# Main_PLL.net
KiCad netlist of a schematic drawn in Altium Designer
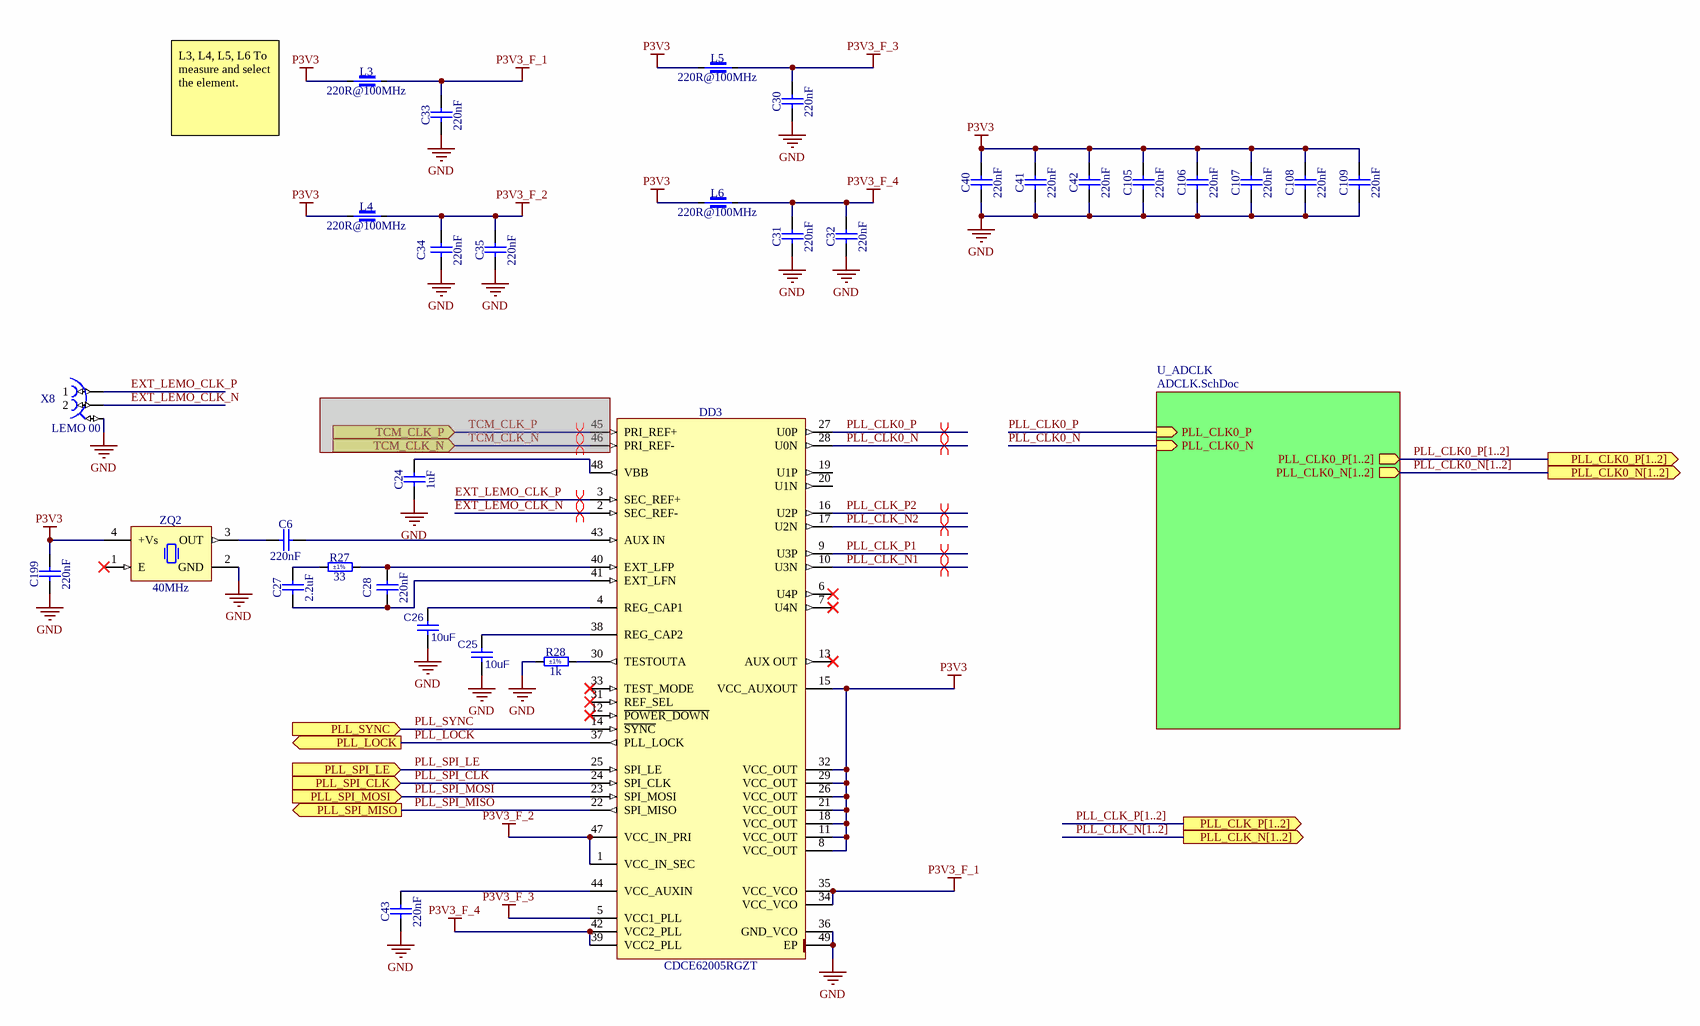
[diagram p0: Main_PLL.SchDoc]

(export (version "E")
  (design (tool "Eeschema 10.0.6"))
  (components
    (comp (ref "C6")
      (value "220nF")
      (footprint "CAPC1005X55N")
      (description "Non-polarised capacitor")
      (fields
        (field (name "PART NUMBER") "CC0402_220NF_16V_10%_X7R")
        (field (name "VOLTAGE") "16V")
        (field (name "AUTHOR") "CERN DEM JLC")
      )
      (libsource (lib "Capacitors") (part "Capacitor - non polarized"))
    )
    (comp (ref "C24")
      (value "1uF")
      (footprint "CAPC2012X140N")
      (description "Non-polarised capacitor")
      (fields
        (field (name "PART NUMBER") "CC0805_1UF_25V_10%_X7R")
        (field (name "VOLTAGE") "25V")
        (field (name "AUTHOR") "CERN DEM JLC")
      )
      (libsource (lib "Capacitors") (part "Capacitor - non polarized"))
    )
    (comp (ref "C25")
      (value "10uF")
      (footprint "CAPC1005X70N")
      (description "Non-polarised capacitor")
      (fields
        (field (name "PART NUMBER") "CC0402_10UF_6.3V_20%_X5R")
        (field (name "VOLTAGE") "6.3V")
        (field (name "AUTHOR") "CERN DEM JLC")
      )
      (libsource (lib "Capacitors") (part "Capacitor - non polarized"))
    )
    (comp (ref "C26")
      (value "10uF")
      (footprint "CAPC1005X70N")
      (description "Non-polarised capacitor")
      (fields
        (field (name "PART NUMBER") "CC0402_10UF_6.3V_20%_X5R")
        (field (name "VOLTAGE") "6.3V")
        (field (name "AUTHOR") "CERN DEM JLC")
      )
      (libsource (lib "Capacitors") (part "Capacitor - non polarized"))
    )
    (comp (ref "C27")
      (value "2.2uF")
      (footprint "CAPC2012X140N")
      (description "Non-polarised capacitor")
      (fields
        (field (name "PART NUMBER") "CC0805_2.2UF_50V_10%_X7R")
        (field (name "VOLTAGE") "50V")
        (field (name "AUTHOR") "CERN DEM JLC")
      )
      (libsource (lib "Capacitors") (part "Capacitor - non polarized"))
    )
    (comp (ref "C28")
      (value "220nF")
      (footprint "CAPC2012X135N")
      (description "Non-polarised capacitor")
      (fields
        (field (name "PART NUMBER") "CC0805_220NF_50V_10%_X7R")
        (field (name "VOLTAGE") "50V")
        (field (name "AUTHOR") "CERN DEM JLC")
      )
      (libsource (lib "Capacitors") (part "Capacitor - non polarized"))
    )
    (comp (ref "C30")
      (value "220nF")
      (footprint "CAPC2012X135N")
      (description "Non-polarised capacitor")
      (fields
        (field (name "PART NUMBER") "CC0805_220NF_50V_10%_X7R")
        (field (name "VOLTAGE") "50V")
        (field (name "AUTHOR") "CERN DEM JLC")
      )
      (libsource (lib "Capacitors") (part "Capacitor - non polarized"))
    )
    (comp (ref "C31")
      (value "220nF")
      (footprint "CAPC2012X135N")
      (description "Non-polarised capacitor")
      (fields
        (field (name "PART NUMBER") "CC0805_220NF_50V_10%_X7R")
        (field (name "VOLTAGE") "50V")
        (field (name "AUTHOR") "CERN DEM JLC")
      )
      (libsource (lib "Capacitors") (part "Capacitor - non polarized"))
    )
    (comp (ref "C32")
      (value "220nF")
      (footprint "CAPC2012X135N")
      (description "Non-polarised capacitor")
      (fields
        (field (name "PART NUMBER") "CC0805_220NF_50V_10%_X7R")
        (field (name "VOLTAGE") "50V")
        (field (name "AUTHOR") "CERN DEM JLC")
      )
      (libsource (lib "Capacitors") (part "Capacitor - non polarized"))
    )
    (comp (ref "C33")
      (value "220nF")
      (footprint "CAPC2012X135N")
      (description "Non-polarised capacitor")
      (fields
        (field (name "PART NUMBER") "CC0805_220NF_50V_10%_X7R")
        (field (name "VOLTAGE") "50V")
        (field (name "AUTHOR") "CERN DEM JLC")
      )
      (libsource (lib "Capacitors") (part "Capacitor - non polarized"))
    )
    (comp (ref "C34")
      (value "220nF")
      (footprint "CAPC2012X135N")
      (description "Non-polarised capacitor")
      (fields
        (field (name "PART NUMBER") "CC0805_220NF_50V_10%_X7R")
        (field (name "VOLTAGE") "50V")
        (field (name "AUTHOR") "CERN DEM JLC")
      )
      (libsource (lib "Capacitors") (part "Capacitor - non polarized"))
    )
    (comp (ref "C35")
      (value "220nF")
      (footprint "CAPC2012X135N")
      (description "Non-polarised capacitor")
      (fields
        (field (name "PART NUMBER") "CC0805_220NF_50V_10%_X7R")
        (field (name "VOLTAGE") "50V")
        (field (name "AUTHOR") "CERN DEM JLC")
      )
      (libsource (lib "Capacitors") (part "Capacitor - non polarized"))
    )
    (comp (ref "C40")
      (value "220nF")
      (footprint "CAPC1005X55N")
      (description "Non-polarised capacitor")
      (fields
        (field (name "PART NUMBER") "CC0402_220NF_16V_10%_X7R")
        (field (name "VOLTAGE") "16V")
        (field (name "AUTHOR") "CERN DEM JLC")
      )
      (libsource (lib "Capacitors") (part "Capacitor - non polarized"))
    )
    (comp (ref "C41")
      (value "220nF")
      (footprint "CAPC1005X55N")
      (description "Non-polarised capacitor")
      (fields
        (field (name "PART NUMBER") "CC0402_220NF_16V_10%_X7R")
        (field (name "VOLTAGE") "16V")
        (field (name "AUTHOR") "CERN DEM JLC")
      )
      (libsource (lib "Capacitors") (part "Capacitor - non polarized"))
    )
    (comp (ref "C42")
      (value "220nF")
      (footprint "CAPC1005X55N")
      (description "Non-polarised capacitor")
      (fields
        (field (name "PART NUMBER") "CC0402_220NF_16V_10%_X7R")
        (field (name "VOLTAGE") "16V")
        (field (name "AUTHOR") "CERN DEM JLC")
      )
      (libsource (lib "Capacitors") (part "Capacitor - non polarized"))
    )
    (comp (ref "C43")
      (value "220nF")
      (footprint "CAPC2012X135N")
      (description "Non-polarised capacitor")
      (fields
        (field (name "PART NUMBER") "CC0805_220NF_50V_10%_X7R")
        (field (name "VOLTAGE") "50V")
        (field (name "AUTHOR") "CERN DEM JLC")
      )
      (libsource (lib "Capacitors") (part "Capacitor - non polarized"))
    )
    (comp (ref "C105")
      (value "220nF")
      (footprint "CAPC1005X55N")
      (description "Non-polarised capacitor")
      (fields
        (field (name "PART NUMBER") "CC0402_220NF_16V_10%_X7R")
        (field (name "VOLTAGE") "16V")
        (field (name "AUTHOR") "CERN DEM JLC")
      )
      (libsource (lib "Capacitors") (part "Capacitor - non polarized"))
    )
    (comp (ref "C106")
      (value "220nF")
      (footprint "CAPC1005X55N")
      (description "Non-polarised capacitor")
      (fields
        (field (name "PART NUMBER") "CC0402_220NF_16V_10%_X7R")
        (field (name "VOLTAGE") "16V")
        (field (name "AUTHOR") "CERN DEM JLC")
      )
      (libsource (lib "Capacitors") (part "Capacitor - non polarized"))
    )
    (comp (ref "C107")
      (value "220nF")
      (footprint "CAPC1005X55N")
      (description "Non-polarised capacitor")
      (fields
        (field (name "PART NUMBER") "CC0402_220NF_16V_10%_X7R")
        (field (name "VOLTAGE") "16V")
        (field (name "AUTHOR") "CERN DEM JLC")
      )
      (libsource (lib "Capacitors") (part "Capacitor - non polarized"))
    )
    (comp (ref "C108")
      (value "220nF")
      (footprint "CAPC1005X55N")
      (description "Non-polarised capacitor")
      (fields
        (field (name "PART NUMBER") "CC0402_220NF_16V_10%_X7R")
        (field (name "VOLTAGE") "16V")
        (field (name "AUTHOR") "CERN DEM JLC")
      )
      (libsource (lib "Capacitors") (part "Capacitor - non polarized"))
    )
    (comp (ref "C109")
      (value "220nF")
      (footprint "CAPC1005X55N")
      (description "Non-polarised capacitor")
      (fields
        (field (name "PART NUMBER") "CC0402_220NF_16V_10%_X7R")
        (field (name "VOLTAGE") "16V")
        (field (name "AUTHOR") "CERN DEM JLC")
      )
      (libsource (lib "Capacitors") (part "Capacitor - non polarized"))
    )
    (comp (ref "C199")
      (value "220nF")
      (footprint "CAPC2012X135N")
      (description "Non-polarised capacitor")
      (fields
        (field (name "PART NUMBER") "CC0805_220NF_50V_10%_X7R")
        (field (name "VOLTAGE") "50V")
        (field (name "AUTHOR") "CERN DEM JLC")
      )
      (libsource (lib "Capacitors") (part "Capacitor - non polarized"))
    )
    (comp (ref "DD3")
      (value "CDCE62005RGZT")
      (footprint "QFN50P700X700X100-49N-S570")
      (description "5/10 Outputs Clock Generator/Jitter Cleaner with Integrated Dual VCO")
      (fields
        (field (name "MANUFACTURER") "TEXAS INSTRUMENTS")
        (field (name "MANUFACTURER PART NUMBER") "CDCE62005RGZ")
        (field (name "AUTHOR") "CERN DEM JLC")
      )
      (libsource (lib "ICs And Semiconductors") (part "CDCE62005RGZT"))
    )
    (comp (ref "L3")
      (value "220R@100MHz")
      (footprint "INDC2012X105N")
      (fields
        (field (name "PART NUMBER") "IND0805_TDK_MPZ2012S221A")
        (field (name "POWER") "3A")
        (field (name "TOLERANCE") "±25%")
        (field (name "AUTHOR") "CERN DEM HF")
      )
      (libsource (lib "Inductors & Transformers") (part "Ferrite Bead"))
    )
    (comp (ref "L4")
      (value "220R@100MHz")
      (footprint "INDC2012X105N")
      (fields
        (field (name "PART NUMBER") "IND0805_TDK_MPZ2012S221A")
        (field (name "POWER") "3A")
        (field (name "TOLERANCE") "±25%")
        (field (name "AUTHOR") "CERN DEM HF")
      )
      (libsource (lib "Inductors & Transformers") (part "Ferrite Bead"))
    )
    (comp (ref "L5")
      (value "220R@100MHz")
      (footprint "INDC2012X105N")
      (fields
        (field (name "PART NUMBER") "IND0805_TDK_MPZ2012S221A")
        (field (name "POWER") "3A")
        (field (name "TOLERANCE") "±25%")
        (field (name "AUTHOR") "CERN DEM HF")
      )
      (libsource (lib "Inductors & Transformers") (part "Ferrite Bead"))
    )
    (comp (ref "L6")
      (value "220R@100MHz")
      (footprint "INDC2012X105N")
      (fields
        (field (name "PART NUMBER") "IND0805_TDK_MPZ2012S221A")
        (field (name "POWER") "3A")
        (field (name "TOLERANCE") "±25%")
        (field (name "AUTHOR") "CERN DEM HF")
      )
      (libsource (lib "Inductors & Transformers") (part "Ferrite Bead"))
    )
    (comp (ref "R27")
      (value "33")
      (footprint "RESC1005X40N")
      (description "Resistor - 1%")
      (fields
        (field (name "TOLERANCE") "±1%")
        (field (name "PART NUMBER") "R0402_33R_1%_0.0625W_100PPM")
        (field (name "POWER") "0.0625W")
        (field (name "AUTHOR") "CERN DEM JLC")
      )
      (libsource (lib "Resistors") (part "Resistor - 1%"))
    )
    (comp (ref "R28")
      (value "1k")
      (footprint "RESC1005X40N")
      (description "Resistor - 1%")
      (fields
        (field (name "TOLERANCE") "±1%")
        (field (name "PART NUMBER") "R0402_1K_1%_0.0625W_100PPM")
        (field (name "POWER") "0.0625W")
        (field (name "AUTHOR") "CERN DEM JLC")
      )
      (libsource (lib "Resistors") (part "Resistor - 1%"))
    )
    (comp (ref "X8")
      (value "LEMO 00")
      (footprint "LEMO_EPG.00.302.NLN")
      (fields
        (field (name "PART NUMBER") "LEMO_EPG.00.302.NLN")
        (field (name "MANUFACTURER") "LEMO")
        (field (name "MANUFACTURER PART NUMBER") "EPG.00.302.NLN")
        (field (name "AUTHOR") "CERN DEM JLC")
      )
      (libsource (lib "Connectors") (part "Coax_2Female_1Shield"))
    )
    (comp (ref "ZQ2")
      (value "40MHz")
      (footprint "OSC_IQD_CFPS-73")
      (description "Oscillator 4 pins 1=E 2=GND 3=OUT 4=+Vs")
      (fields
        (field (name "PART NUMBER") "OSC_40MHZ_IQD_LFSPXO018042")
        (field (name "MANUFACTURER") "IQD FREQUENCY PRODUCTS")
        (field (name "AUTHOR") "CERN DEM JLC")
      )
      (libsource (lib "ICs And Semiconductors") (part "Oscillator 1E 2GND 3OUT 4Vs"))
    )
  )
  (nets
    (net (code "5") (name "/EXT_LEMO_CLK_N") (class "Default")
      (node (ref "DD3") (pin "2") (pinfunction "SEC_REF-_2") (pintype "input"))
      (node (ref "X8") (pin "2") (pinfunction "2_2") (pintype "bidirectional"))
    )
    (net (code "6") (name "/EXT_LEMO_CLK_P") (class "Default")
      (node (ref "DD3") (pin "3") (pinfunction "SEC_REF+_3") (pintype "input"))
      (node (ref "X8") (pin "1") (pinfunction "1_1") (pintype "bidirectional"))
    )
    (net (code "7") (name "/PLL_CLK0_N") (class "Default")
      (node (ref "DD3") (pin "28") (pinfunction "U0N_28") (pintype "output"))
    )
    (net (code "9") (name "/PLL_CLK0_P") (class "Default")
      (node (ref "DD3") (pin "27") (pinfunction "U0P_27") (pintype "output"))
    )
    (net (code "11") (name "/PLL_CLK_N1") (class "Default")
      (node (ref "DD3") (pin "10") (pinfunction "U3N_10") (pintype "output"))
    )
    (net (code "12") (name "/PLL_CLK_N2") (class "Default")
      (node (ref "DD3") (pin "17") (pinfunction "U2N_17") (pintype "output"))
    )
    (net (code "14") (name "/PLL_CLK_P1") (class "Default")
      (node (ref "DD3") (pin "9") (pinfunction "U3P_9") (pintype "output"))
    )
    (net (code "15") (name "/PLL_CLK_P2") (class "Default")
      (node (ref "DD3") (pin "16") (pinfunction "U2P_16") (pintype "output"))
    )
    (net (code "17") (name "/PLL_LOCK") (class "Default")
      (node (ref "DD3") (pin "37") (pinfunction "PLL_LOCK_37") (pintype "output"))
    )
    (net (code "18") (name "/PLL_SPI_CLK") (class "Default")
      (node (ref "DD3") (pin "24") (pinfunction "SPI_CLK_24") (pintype "input"))
    )
    (net (code "19") (name "/PLL_SPI_LE") (class "Default")
      (node (ref "DD3") (pin "25") (pinfunction "SPI_LE_25") (pintype "input"))
    )
    (net (code "20") (name "/PLL_SPI_MISO") (class "Default")
      (node (ref "DD3") (pin "22") (pinfunction "SPI_MISO_22") (pintype "output"))
    )
    (net (code "21") (name "/PLL_SPI_MOSI") (class "Default")
      (node (ref "DD3") (pin "23") (pinfunction "SPI_MOSI_23") (pintype "input"))
    )
    (net (code "22") (name "/PLL_SYNC") (class "Default")
      (node (ref "DD3") (pin "14") (pinfunction "~{SYNC}_14") (pintype "input"))
    )
    (net (code "23") (name "/TCM_CLK_N") (class "Default")
      (node (ref "DD3") (pin "46") (pinfunction "PRI_REF-_46") (pintype "input"))
    )
    (net (code "24") (name "/TCM_CLK_P") (class "Default")
      (node (ref "DD3") (pin "45") (pinfunction "PRI_REF+_45") (pintype "input"))
    )
    (net (code "25") (name "GND") (class "Default")
      (node (ref "C105") (pin "1") (pinfunction "1_1") (pintype "passive"))
      (node (ref "C106") (pin "1") (pinfunction "1_1") (pintype "passive"))
      (node (ref "C107") (pin "1") (pinfunction "1_1") (pintype "passive"))
      (node (ref "C108") (pin "1") (pinfunction "1_1") (pintype "passive"))
      (node (ref "C109") (pin "1") (pinfunction "1_1") (pintype "passive"))
      (node (ref "C199") (pin "1") (pinfunction "1_1") (pintype "passive"))
      (node (ref "C24") (pin "1") (pinfunction "1_1") (pintype "passive"))
      (node (ref "C25") (pin "1") (pinfunction "1_1") (pintype "passive"))
      (node (ref "C26") (pin "1") (pinfunction "1_1") (pintype "passive"))
      (node (ref "C30") (pin "1") (pinfunction "1_1") (pintype "passive"))
      (node (ref "C31") (pin "1") (pinfunction "1_1") (pintype "passive"))
      (node (ref "C32") (pin "1") (pinfunction "1_1") (pintype "passive"))
      (node (ref "C33") (pin "1") (pinfunction "1_1") (pintype "passive"))
      (node (ref "C34") (pin "1") (pinfunction "1_1") (pintype "passive"))
      (node (ref "C35") (pin "1") (pinfunction "1_1") (pintype "passive"))
      (node (ref "C40") (pin "1") (pinfunction "1_1") (pintype "passive"))
      (node (ref "C41") (pin "1") (pinfunction "1_1") (pintype "passive"))
      (node (ref "C42") (pin "1") (pinfunction "1_1") (pintype "passive"))
      (node (ref "C43") (pin "1") (pinfunction "1_1") (pintype "passive"))
      (node (ref "DD3") (pin "36") (pinfunction "GND_VCO_36") (pintype "power_in"))
      (node (ref "DD3") (pin "49") (pinfunction "EP_49") (pintype "power_in"))
      (node (ref "R28") (pin "1") (pinfunction "1_1") (pintype "passive"))
      (node (ref "X8") (pin "3") (pinfunction "3_3") (pintype "bidirectional"))
      (node (ref "ZQ2") (pin "2") (pinfunction "GND_2") (pintype "power_in"))
    )
    (net (code "26") (name "Net-(C27-Pad2)") (class "Default")
      (node (ref "C27") (pin "2") (pinfunction "2_2") (pintype "passive"))
      (node (ref "R27") (pin "1") (pinfunction "1_1") (pintype "passive"))
    )
    (net (code "27") (name "Net-(DD3-AUX_IN)") (class "Default")
      (node (ref "C6") (pin "2") (pinfunction "2_2") (pintype "passive"))
      (node (ref "DD3") (pin "43") (pinfunction "AUX_IN_43") (pintype "input"))
    )
    (net (code "28") (name "Net-(DD3-EXT_LFN)") (class "Default")
      (node (ref "C27") (pin "1") (pinfunction "1_1") (pintype "passive"))
      (node (ref "C28") (pin "1") (pinfunction "1_1") (pintype "passive"))
      (node (ref "DD3") (pin "41") (pinfunction "EXT_LFN_41") (pintype "input"))
    )
    (net (code "29") (name "Net-(DD3-EXT_LFP)") (class "Default")
      (node (ref "C28") (pin "2") (pinfunction "2_2") (pintype "passive"))
      (node (ref "DD3") (pin "40") (pinfunction "EXT_LFP_40") (pintype "input"))
      (node (ref "R27") (pin "2") (pinfunction "2_2") (pintype "passive"))
    )
    (net (code "30") (name "Net-(DD3-REG_CAP1)") (class "Default")
      (node (ref "C26") (pin "2") (pinfunction "2_2") (pintype "passive"))
      (node (ref "DD3") (pin "4") (pinfunction "REG_CAP1_4") (pintype "passive"))
    )
    (net (code "31") (name "Net-(DD3-REG_CAP2)") (class "Default")
      (node (ref "C25") (pin "2") (pinfunction "2_2") (pintype "passive"))
      (node (ref "DD3") (pin "38") (pinfunction "REG_CAP2_38") (pintype "passive"))
    )
    (net (code "32") (name "Net-(DD3-TESTOUTA)") (class "Default")
      (node (ref "DD3") (pin "30") (pinfunction "TESTOUTA_30") (pintype "output"))
      (node (ref "R28") (pin "2") (pinfunction "2_2") (pintype "passive"))
    )
    (net (code "33") (name "Net-(DD3-VBB)") (class "Default")
      (node (ref "C24") (pin "2") (pinfunction "2_2") (pintype "passive"))
      (node (ref "DD3") (pin "48") (pinfunction "VBB_48") (pintype "output"))
    )
    (net (code "34") (name "Net-(DD3-VCC_AUXIN)") (class "Default")
      (node (ref "C43") (pin "2") (pinfunction "2_2") (pintype "passive"))
      (node (ref "DD3") (pin "44") (pinfunction "VCC_AUXIN_44") (pintype "power_in"))
    )
    (net (code "35") (name "Net-(ZQ2-OUT)") (class "Default")
      (node (ref "C6") (pin "1") (pinfunction "1_1") (pintype "passive"))
      (node (ref "ZQ2") (pin "3") (pinfunction "OUT_3") (pintype "output"))
    )
    (net (code "36") (name "P3V3") (class "Default")
      (node (ref "C105") (pin "2") (pinfunction "2_2") (pintype "passive"))
      (node (ref "C106") (pin "2") (pinfunction "2_2") (pintype "passive"))
      (node (ref "C107") (pin "2") (pinfunction "2_2") (pintype "passive"))
      (node (ref "C108") (pin "2") (pinfunction "2_2") (pintype "passive"))
      (node (ref "C109") (pin "2") (pinfunction "2_2") (pintype "passive"))
      (node (ref "C199") (pin "2") (pinfunction "2_2") (pintype "passive"))
      (node (ref "C40") (pin "2") (pinfunction "2_2") (pintype "passive"))
      (node (ref "C41") (pin "2") (pinfunction "2_2") (pintype "passive"))
      (node (ref "C42") (pin "2") (pinfunction "2_2") (pintype "passive"))
      (node (ref "DD3") (pin "11") (pinfunction "VCC_OUT_11") (pintype "power_in"))
      (node (ref "DD3") (pin "15") (pinfunction "VCC_AUXOUT_15") (pintype "power_in"))
      (node (ref "DD3") (pin "18") (pinfunction "VCC_OUT_18") (pintype "power_in"))
      (node (ref "DD3") (pin "21") (pinfunction "VCC_OUT_21") (pintype "power_in"))
      (node (ref "DD3") (pin "26") (pinfunction "VCC_OUT_26") (pintype "power_in"))
      (node (ref "DD3") (pin "29") (pinfunction "VCC_OUT_29") (pintype "power_in"))
      (node (ref "DD3") (pin "32") (pinfunction "VCC_OUT_32") (pintype "power_in"))
      (node (ref "DD3") (pin "8") (pinfunction "VCC_OUT_8") (pintype "power_in"))
      (node (ref "L3") (pin "1") (pinfunction "1_1") (pintype "passive"))
      (node (ref "L4") (pin "1") (pinfunction "1_1") (pintype "passive"))
      (node (ref "L5") (pin "1") (pinfunction "1_1") (pintype "passive"))
      (node (ref "L6") (pin "1") (pinfunction "1_1") (pintype "passive"))
      (node (ref "ZQ2") (pin "4") (pinfunction "+Vs_4") (pintype "power_in"))
    )
    (net (code "37") (name "P3V3_F_1") (class "Default")
      (node (ref "C33") (pin "2") (pinfunction "2_2") (pintype "passive"))
      (node (ref "DD3") (pin "34") (pinfunction "VCC_VCO_34") (pintype "power_in"))
      (node (ref "DD3") (pin "35") (pinfunction "VCC_VCO_35") (pintype "power_in"))
      (node (ref "L3") (pin "2") (pinfunction "2_2") (pintype "passive"))
    )
    (net (code "38") (name "P3V3_F_2") (class "Default")
      (node (ref "C34") (pin "2") (pinfunction "2_2") (pintype "passive"))
      (node (ref "C35") (pin "2") (pinfunction "2_2") (pintype "passive"))
      (node (ref "DD3") (pin "1") (pinfunction "VCC_IN_SEC_1") (pintype "power_in"))
      (node (ref "DD3") (pin "47") (pinfunction "VCC_IN_PRI_47") (pintype "power_in"))
      (node (ref "L4") (pin "2") (pinfunction "2_2") (pintype "passive"))
    )
    (net (code "39") (name "P3V3_F_3") (class "Default")
      (node (ref "C30") (pin "2") (pinfunction "2_2") (pintype "passive"))
      (node (ref "DD3") (pin "5") (pinfunction "VCC1_PLL_5") (pintype "power_in"))
      (node (ref "L5") (pin "2") (pinfunction "2_2") (pintype "passive"))
    )
    (net (code "40") (name "P3V3_F_4") (class "Default")
      (node (ref "C31") (pin "2") (pinfunction "2_2") (pintype "passive"))
      (node (ref "C32") (pin "2") (pinfunction "2_2") (pintype "passive"))
      (node (ref "DD3") (pin "39") (pinfunction "VCC2_PLL_39") (pintype "power_in"))
      (node (ref "DD3") (pin "42") (pinfunction "VCC2_PLL_42") (pintype "power_in"))
      (node (ref "L6") (pin "2") (pinfunction "2_2") (pintype "passive"))
    )
    (net (code "41") (name "unconnected-(DD3-AUX_OUT-Pad13)") (class "Default")
      (node (ref "DD3") (pin "13") (pinfunction "AUX_OUT_13") (pintype "output+no_connect"))
    )
    (net (code "42") (name "unconnected-(DD3-REF_SEL-Pad31)") (class "Default")
      (node (ref "DD3") (pin "31") (pinfunction "REF_SEL_31") (pintype "input+no_connect"))
    )
    (net (code "43") (name "unconnected-(DD3-TEST_MODE-Pad33)") (class "Default")
      (node (ref "DD3") (pin "33") (pinfunction "TEST_MODE_33") (pintype "input+no_connect"))
    )
    (net (code "44") (name "unconnected-(DD3-U1N-Pad20)") (class "Default")
      (node (ref "DD3") (pin "20") (pinfunction "U1N_20") (pintype "output"))
    )
    (net (code "45") (name "unconnected-(DD3-U1P-Pad19)") (class "Default")
      (node (ref "DD3") (pin "19") (pinfunction "U1P_19") (pintype "output"))
    )
    (net (code "46") (name "unconnected-(DD3-U4N-Pad7)") (class "Default")
      (node (ref "DD3") (pin "7") (pinfunction "U4N_7") (pintype "output+no_connect"))
    )
    (net (code "47") (name "unconnected-(DD3-U4P-Pad6)") (class "Default")
      (node (ref "DD3") (pin "6") (pinfunction "U4P_6") (pintype "output+no_connect"))
    )
    (net (code "48") (name "unconnected-(DD3-~{POWER_DOWN}-Pad12)") (class "Default")
      (node (ref "DD3") (pin "12") (pinfunction "~{POWER_DOWN}_12") (pintype "input+no_connect"))
    )
    (net (code "49") (name "unconnected-(ZQ2-E-Pad1)") (class "Default")
      (node (ref "ZQ2") (pin "1") (pinfunction "E_1") (pintype "input+no_connect"))
    )
  )
)
